# short_circuit_protection.net
KiCad netlist of a schematic drawn in Altium Designer
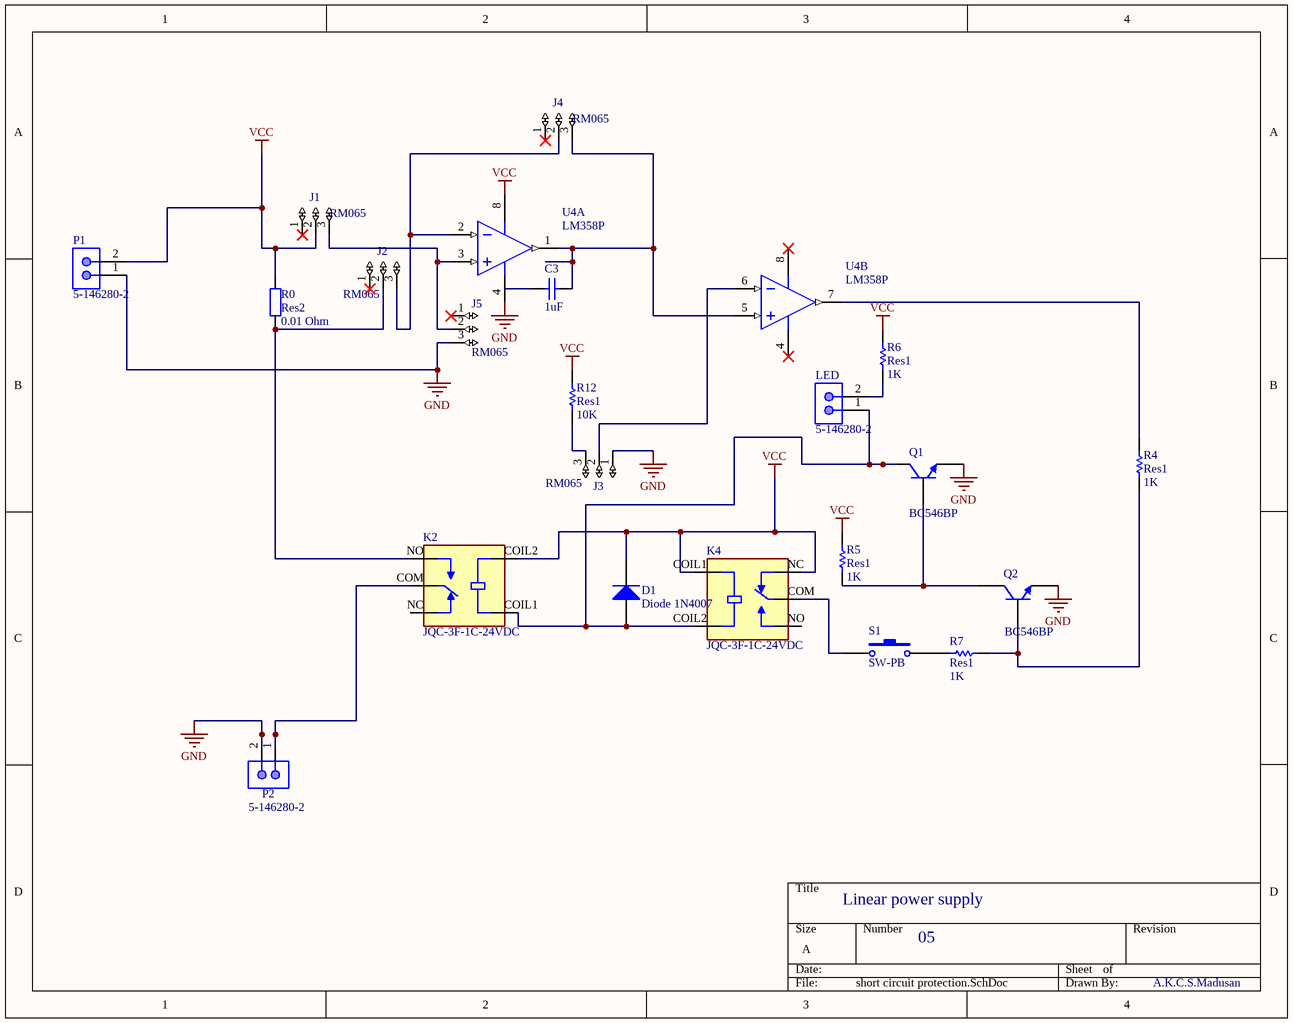
[diagram p0: short circuit protection.SchDoc]

(export (version "E")
  (design (tool "Eeschema 10.0.6"))
  (components
    (comp (ref "C3")
      (value "Capacitor")
      (fields (field (name "C3") "1uF"))
      (libsource (lib "Simulation Generic Components") (part "Capacitor"))
    )
    (comp (ref "D1")
      (value "Diode 1N4007")
      (footprint "DO-41")
      (description "1 Amp General Purpose Rectifier")
      (fields (field (name "PUBLISHER") "Altium Limited"))
      (libsource (lib "Miscellaneous Devices") (part "Diode 1N4007"))
    )
    (comp (ref "J1")
      (value "RM065")
      (footprint "RM065")
      (description "Circuit Breaker Thermal 6.5A 240V AC 60V DC Rocker Panel Mount, Snap-In")
      (fields (field (name "MP") "RM-065") (field (name "MF") "Vishay"))
      (libsource (lib "RM065") (part "RM065"))
    )
    (comp (ref "J2")
      (value "RM065")
      (footprint "RM065")
      (description "Circuit Breaker Thermal 6.5A 240V AC 60V DC Rocker Panel Mount, Snap-In")
      (fields (field (name "MP") "RM-065") (field (name "MF") "Vishay"))
      (libsource (lib "RM065") (part "RM065"))
    )
    (comp (ref "J3")
      (value "RM065")
      (footprint "RM065")
      (description "Circuit Breaker Thermal 6.5A 240V AC 60V DC Rocker Panel Mount, Snap-In")
      (fields (field (name "MP") "RM-065") (field (name "MF") "Vishay"))
      (libsource (lib "RM065") (part "RM065"))
    )
    (comp (ref "J4")
      (value "RM065")
      (footprint "RM065")
      (description "Circuit Breaker Thermal 6.5A 240V AC 60V DC Rocker Panel Mount, Snap-In")
      (fields (field (name "MP") "RM-065") (field (name "MF") "Vishay"))
      (libsource (lib "RM065") (part "RM065"))
    )
    (comp (ref "J5")
      (value "RM065")
      (footprint "RM065")
      (description "Circuit Breaker Thermal 6.5A 240V AC 60V DC Rocker Panel Mount, Snap-In")
      (fields (field (name "MP") "RM-065") (field (name "MF") "Vishay"))
      (libsource (lib "RM065") (part "RM065"))
    )
    (comp (ref "K2")
      (value "JQC-3F-1C-24VDC")
      (footprint "RELAY_JQC-3F-1C-24VDC")
      (description "Miniature PCB Relay 24VDC, 10A 250VAC, 15A 125VAC, 10A 250VAC")
      (libsource (lib "") (part "JQC-3F-1C-24VDC_1"))
    )
    (comp (ref "K4")
      (value "JQC-3F-1C-24VDC")
      (footprint "RELAY_JQC-3F-1C-24VDC")
      (description "Miniature PCB Relay 24VDC, 10A 250VAC, 15A 125VAC, 10A 250VAC")
      (libsource (lib "JQC-3F-1C-24VDC") (part "JQC-3F-1C-24VDC"))
    )
    (comp (ref "LED")
      (value "5-146280-2")
      (footprint "TECO-5-146280-2_V")
      (fields (field (name "MANUFACTURER") "TE Connectivity"))
      (libsource (lib "Altium Content Vault") (part "CN-1P-M-R2"))
    )
    (comp (ref "P1")
      (value "5-146280-2")
      (footprint "TECO-5-146280-2_V")
      (fields (field (name "MANUFACTURER") "TE Connectivity"))
      (libsource (lib "Altium Content Vault") (part "CN-1P-M-R2"))
    )
    (comp (ref "P2")
      (value "5-146280-2")
      (footprint "TECO-5-146280-2_V")
      (fields (field (name "MANUFACTURER") "TE Connectivity"))
      (libsource (lib "") (part "CN-1P-M-R2_1"))
    )
    (comp (ref "Q1")
      (value "BC546BP")
      (footprint "TO-92A")
      (description "NPN General Purpose Amplifier")
      (fields (field (name "PUBLISHER") "Altium Limited"))
      (libsource (lib "Miscellaneous Devices") (part "2N3904"))
    )
    (comp (ref "Q2")
      (value "BC546BP")
      (footprint "TO-92A")
      (description "NPN General Purpose Amplifier")
      (fields (field (name "PUBLISHER") "Altium Limited"))
      (libsource (lib "Miscellaneous Devices") (part "2N3904"))
    )
    (comp (ref "R0")
      (value "Res2")
      (footprint "AXIAL-0.4")
      (description "Resistor")
      (fields (field (name "ALTIUM_VALUE") "0.01 Ohm") (field (name "PUBLISHER") "Altium Limited"))
      (libsource (lib "Miscellaneous Devices") (part "Res2"))
    )
    (comp (ref "R4")
      (value "Res1")
      (footprint "AXIAL-0.3")
      (description "Resistor")
      (fields (field (name "ALTIUM_VALUE") "1K") (field (name "PUBLISHER") "Altium Limited"))
      (libsource (lib "Miscellaneous Devices") (part "Res1"))
    )
    (comp (ref "R5")
      (value "Res1")
      (footprint "AXIAL-0.3")
      (description "Resistor")
      (fields (field (name "ALTIUM_VALUE") "1K") (field (name "PUBLISHER") "Altium Limited"))
      (libsource (lib "Miscellaneous Devices") (part "Res1"))
    )
    (comp (ref "R6")
      (value "Res1")
      (footprint "AXIAL-0.3")
      (description "Resistor")
      (fields (field (name "ALTIUM_VALUE") "1K") (field (name "PUBLISHER") "Altium Limited"))
      (libsource (lib "Miscellaneous Devices") (part "Res1"))
    )
    (comp (ref "R7")
      (value "Res1")
      (footprint "AXIAL-0.3")
      (description "Resistor")
      (fields (field (name "ALTIUM_VALUE") "1K") (field (name "PUBLISHER") "Altium Limited"))
      (libsource (lib "Miscellaneous Devices") (part "Res1"))
    )
    (comp (ref "R12")
      (value "Res1")
      (footprint "AXIAL-0.3")
      (description "Resistor")
      (fields (field (name "ALTIUM_VALUE") "10K") (field (name "PUBLISHER") "Altium Limited"))
      (libsource (lib "Miscellaneous Devices") (part "Res1"))
    )
    (comp (ref "S1")
      (value "SW-PB")
      (footprint "SPST-2")
      (description "Switch")
      (fields (field (name "PUBLISHER") "Altium Limited"))
      (libsource (lib "Miscellaneous Devices") (part "SW-PB"))
    )
    (comp (ref "U4")
      (value "LM358P")
      (footprint "P0008A")
      (description "Dual Operational Amplifier, 3 to 32 V, 0 to 70 degC, 8-Pin PDIP (P), RoHS, Tape and Reel")
      (fields (field (name "MANUFACTURER") "Technik Industrial"))
      (libsource (lib "Altium Content Vault") (part "TI-LM_LPXXX-SO_DIP8"))
    )
  )
  (nets
    (net (code "1") (name "GND") (class "Default")
      (node (ref "J3") (pin "1") (pinfunction "P$1_1") (pintype "bidirectional"))
      (node (ref "J5") (pin "3") (pinfunction "P$3_3") (pintype "bidirectional"))
      (node (ref "P1") (pin "1") (pinfunction "1_1") (pintype "passive"))
      (node (ref "P2") (pin "2") (pinfunction "2_2") (pintype "passive"))
      (node (ref "Q1") (pin "1") (pinfunction "E_1") (pintype "passive"))
      (node (ref "Q2") (pin "1") (pinfunction "E_1") (pintype "passive"))
      (node (ref "U4") (pin "4") (pinfunction "GND_4") (pintype "power_in"))
    )
    (net (code "2") (name "Net-(D1-A)") (class "Default")
      (node (ref "D1") (pin "1") (pinfunction "A_1") (pintype "passive"))
      (node (ref "K2") (pin "COIL1") (pinfunction "COIL1_COIL1") (pintype "passive"))
      (node (ref "K4") (pin "COIL2") (pinfunction "COIL2_COIL2") (pintype "passive"))
      (node (ref "LED") (pin "1") (pinfunction "1_1") (pintype "passive"))
      (node (ref "Q1") (pin "3") (pinfunction "C_3") (pintype "passive"))
    )
    (net (code "3") (name "Net-(J1-P$3)") (class "Default")
      (node (ref "J1") (pin "3") (pinfunction "P$3_3") (pintype "bidirectional"))
      (node (ref "J5") (pin "2") (pinfunction "P$2_2") (pintype "bidirectional"))
      (node (ref "U4") (pin "3") (pinfunction "1IN+_3") (pintype "input"))
    )
    (net (code "4") (name "Net-(J2-P$2)") (class "Default")
      (node (ref "J2") (pin "2") (pinfunction "P$2_2") (pintype "bidirectional"))
      (node (ref "K2") (pin "NO") (pinfunction "NO_NO") (pintype "passive"))
      (node (ref "R0") (pin "1") (pinfunction "1_1") (pintype "passive"))
    )
    (net (code "5") (name "Net-(J2-P$3)") (class "Default")
      (node (ref "J2") (pin "3") (pinfunction "P$3_3") (pintype "bidirectional"))
      (node (ref "J4") (pin "2") (pinfunction "P$2_2") (pintype "bidirectional"))
      (node (ref "U4") (pin "2") (pinfunction "1IN-_2") (pintype "input"))
    )
    (net (code "6") (name "Net-(J3-P$2)") (class "Default")
      (node (ref "J3") (pin "2") (pinfunction "P$2_2") (pintype "bidirectional"))
      (node (ref "U4") (pin "6") (pinfunction "2IN-_6") (pintype "input"))
    )
    (net (code "7") (name "Net-(J3-P$3)") (class "Default")
      (node (ref "J3") (pin "3") (pinfunction "P$3_3") (pintype "bidirectional"))
      (node (ref "R12") (pin "1") (pinfunction "1_1") (pintype "passive"))
    )
    (net (code "8") (name "Net-(J4-P$3)") (class "Default")
      (node (ref "C3") (pin "2") (pinfunction "2_2") (pintype "passive"))
      (node (ref "J4") (pin "3") (pinfunction "P$3_3") (pintype "bidirectional"))
      (node (ref "U4") (pin "1") (pinfunction "1OUT_1") (pintype "output"))
      (node (ref "U4") (pin "5") (pinfunction "2IN+_5") (pintype "input"))
    )
    (net (code "9") (name "Net-(K2-PadCOM)") (class "Default")
      (node (ref "K2") (pin "COM") (pinfunction "COM_COM") (pintype "passive"))
      (node (ref "P2") (pin "1") (pinfunction "1_1") (pintype "passive"))
    )
    (net (code "10") (name "Net-(K4-PadCOM)") (class "Default")
      (node (ref "K4") (pin "COM") (pinfunction "COM_COM") (pintype "passive"))
      (node (ref "S1") (pin "1") (pinfunction "1_1") (pintype "passive"))
    )
    (net (code "11") (name "Net-(LED-Pad2)") (class "Default")
      (node (ref "LED") (pin "2") (pinfunction "2_2") (pintype "passive"))
      (node (ref "R6") (pin "1") (pinfunction "1_1") (pintype "passive"))
    )
    (net (code "12") (name "Net-(Q1-B)") (class "Default")
      (node (ref "Q1") (pin "2") (pinfunction "B_2") (pintype "passive"))
      (node (ref "Q2") (pin "3") (pinfunction "C_3") (pintype "passive"))
      (node (ref "R5") (pin "1") (pinfunction "1_1") (pintype "passive"))
    )
    (net (code "13") (name "Net-(Q2-B)") (class "Default")
      (node (ref "Q2") (pin "2") (pinfunction "B_2") (pintype "passive"))
      (node (ref "R4") (pin "1") (pinfunction "1_1") (pintype "passive"))
      (node (ref "R7") (pin "2") (pinfunction "2_2") (pintype "passive"))
    )
    (net (code "14") (name "Net-(R7-Pad1)") (class "Default")
      (node (ref "R7") (pin "1") (pinfunction "1_1") (pintype "passive"))
      (node (ref "S1") (pin "2") (pinfunction "2_2") (pintype "passive"))
    )
    (net (code "15") (name "Net-(U4B-2OUT)") (class "Default")
      (node (ref "R4") (pin "2") (pinfunction "2_2") (pintype "passive"))
      (node (ref "U4") (pin "7") (pinfunction "2OUT_7") (pintype "output"))
    )
    (net (code "16") (name "VCC") (class "Default")
      (node (ref "D1") (pin "2") (pinfunction "K_2") (pintype "passive"))
      (node (ref "J1") (pin "2") (pinfunction "P$2_2") (pintype "bidirectional"))
      (node (ref "K2") (pin "COIL2") (pinfunction "COIL2_COIL2") (pintype "passive"))
      (node (ref "K4") (pin "COIL1") (pinfunction "COIL1_COIL1") (pintype "passive"))
      (node (ref "K4") (pin "NC") (pinfunction "NC_NC") (pintype "passive"))
      (node (ref "P1") (pin "2") (pinfunction "2_2") (pintype "passive"))
      (node (ref "R0") (pin "2") (pinfunction "2_2") (pintype "passive"))
      (node (ref "R12") (pin "2") (pinfunction "2_2") (pintype "passive"))
      (node (ref "R5") (pin "2") (pinfunction "2_2") (pintype "passive"))
      (node (ref "R6") (pin "2") (pinfunction "2_2") (pintype "passive"))
      (node (ref "U4") (pin "8") (pinfunction "VCC_8") (pintype "power_in"))
    )
    (net (code "17") (name "unconnected-(C3-Pad1)") (class "Default")
      (node (ref "C3") (pin "1") (pinfunction "1_1") (pintype "passive"))
    )
    (net (code "18") (name "unconnected-(J1-P$1-Pad1)") (class "Default")
      (node (ref "J1") (pin "1") (pinfunction "P$1_1") (pintype "bidirectional+no_connect"))
    )
    (net (code "19") (name "unconnected-(J2-P$1-Pad1)") (class "Default")
      (node (ref "J2") (pin "1") (pinfunction "P$1_1") (pintype "bidirectional+no_connect"))
    )
    (net (code "20") (name "unconnected-(J4-P$1-Pad1)") (class "Default")
      (node (ref "J4") (pin "1") (pinfunction "P$1_1") (pintype "bidirectional+no_connect"))
    )
    (net (code "21") (name "unconnected-(J5-P$1-Pad1)") (class "Default")
      (node (ref "J5") (pin "1") (pinfunction "P$1_1") (pintype "bidirectional+no_connect"))
    )
    (net (code "22") (name "unconnected-(K2-PadNC)") (class "Default")
      (node (ref "K2") (pin "NC") (pinfunction "NC_NC") (pintype "passive"))
    )
    (net (code "23") (name "unconnected-(K4-PadNO)") (class "Default")
      (node (ref "K4") (pin "NO") (pinfunction "NO_NO") (pintype "passive"))
    )
    (net (code "24") (name "unconnected-(U4B-GND-Pad4)") (class "Default")
      (node (ref "U4") (pin "4") (pinfunction "GND_4") (pintype "power_in+no_connect"))
    )
    (net (code "25") (name "unconnected-(U4B-VCC-Pad8)") (class "Default")
      (node (ref "U4") (pin "8") (pinfunction "VCC_8") (pintype "power_in+no_connect"))
    )
  )
)
